# SignalGenerator.net
KiCad netlist of a schematic drawn in EAGLE
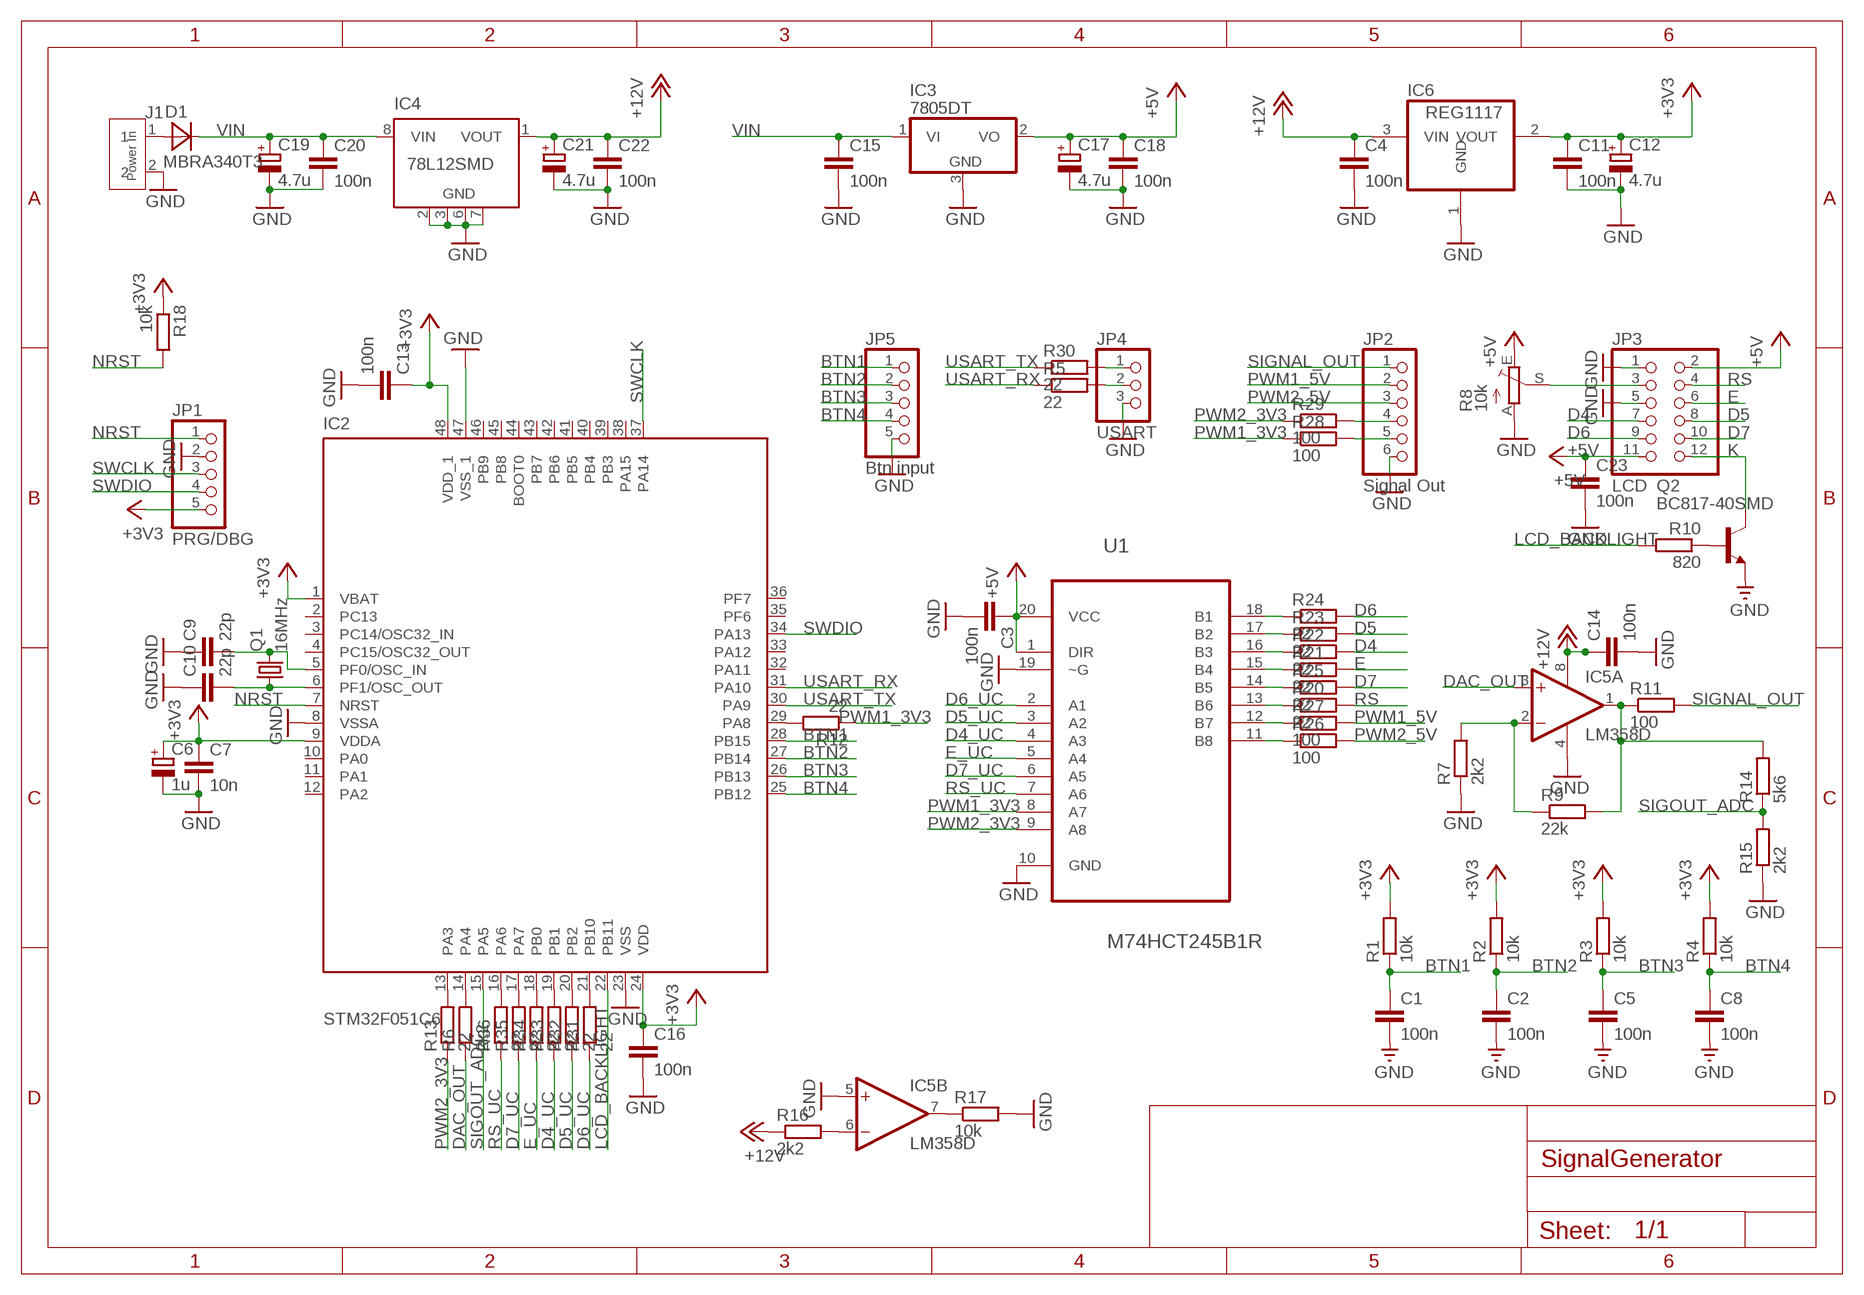
[diagram p0: schematic, sheet 1]

(export (version "E")
  (design (tool "Eeschema 10.0.6"))
  (components
    (comp (ref "C1")
      (value "100n")
      (footprint "eagle-import:C0805")
      (libsource (lib "eagle-import") (part "C-EUC0805"))
    )
    (comp (ref "C2")
      (value "100n")
      (footprint "eagle-import:C0805")
      (libsource (lib "eagle-import") (part "C-EUC0805"))
    )
    (comp (ref "C3")
      (value "100n")
      (footprint "eagle-import:C0805")
      (libsource (lib "eagle-import") (part "C-EUC0805"))
    )
    (comp (ref "C4")
      (value "100n")
      (footprint "eagle-import:C0805")
      (libsource (lib "eagle-import") (part "C-EUC0805"))
    )
    (comp (ref "C5")
      (value "100n")
      (footprint "eagle-import:C0805")
      (libsource (lib "eagle-import") (part "C-EUC0805"))
    )
    (comp (ref "C6")
      (value "1u")
      (footprint "eagle-import:A_3216-18W")
      (libsource (lib "eagle-import") (part "CPOL-EUA/3216-18W"))
    )
    (comp (ref "C7")
      (value "10n")
      (footprint "eagle-import:C0805")
      (libsource (lib "eagle-import") (part "C-EUC0805"))
    )
    (comp (ref "C8")
      (value "100n")
      (footprint "eagle-import:C0805")
      (libsource (lib "eagle-import") (part "C-EUC0805"))
    )
    (comp (ref "C9")
      (value "22p")
      (footprint "eagle-import:C0603")
      (libsource (lib "eagle-import") (part "C-EUC0603"))
    )
    (comp (ref "C10")
      (value "22p")
      (footprint "eagle-import:C0603")
      (libsource (lib "eagle-import") (part "C-EUC0603"))
    )
    (comp (ref "C11")
      (value "100n")
      (footprint "eagle-import:C0805")
      (libsource (lib "eagle-import") (part "C-EUC0805"))
    )
    (comp (ref "C12")
      (value "4.7u")
      (footprint "eagle-import:PANASONIC_A")
      (libsource (lib "eagle-import") (part "CPOL-EUA"))
    )
    (comp (ref "C13")
      (value "100n")
      (footprint "eagle-import:C0805")
      (libsource (lib "eagle-import") (part "C-EUC0805"))
    )
    (comp (ref "C14")
      (value "100n")
      (footprint "eagle-import:C0805")
      (libsource (lib "eagle-import") (part "C-EUC0805"))
    )
    (comp (ref "C15")
      (value "100n")
      (footprint "eagle-import:C0805")
      (libsource (lib "eagle-import") (part "C-EUC0805"))
    )
    (comp (ref "C16")
      (value "100n")
      (footprint "eagle-import:C0805")
      (libsource (lib "eagle-import") (part "C-EUC0805"))
    )
    (comp (ref "C17")
      (value "4.7u")
      (footprint "eagle-import:PANASONIC_B")
      (libsource (lib "eagle-import") (part "CPOL-EUB"))
    )
    (comp (ref "C18")
      (value "100n")
      (footprint "eagle-import:C0805")
      (libsource (lib "eagle-import") (part "C-EUC0805"))
    )
    (comp (ref "C19")
      (value "4.7u")
      (footprint "eagle-import:PANASONIC_B")
      (libsource (lib "eagle-import") (part "CPOL-EUB"))
    )
    (comp (ref "C20")
      (value "100n")
      (footprint "eagle-import:C0805")
      (libsource (lib "eagle-import") (part "C-EUC0805"))
    )
    (comp (ref "C21")
      (value "4.7u")
      (footprint "eagle-import:PANASONIC_A")
      (libsource (lib "eagle-import") (part "CPOL-EUA"))
    )
    (comp (ref "C22")
      (value "100n")
      (footprint "eagle-import:C0805")
      (libsource (lib "eagle-import") (part "C-EUC0805"))
    )
    (comp (ref "C23")
      (value "100n")
      (footprint "eagle-import:C0805")
      (libsource (lib "eagle-import") (part "C-EUC0805"))
    )
    (comp (ref "D1")
      (value "MBRA340T3")
      (footprint "eagle-import:SMA")
      (libsource (lib "eagle-import") (part "MBRA340T3"))
    )
    (comp (ref "IC2")
      (value "STM32F051C6")
      (footprint "eagle-import:LQFP48-7X7")
      (libsource (lib "eagle-import") (part "STM32F051C6"))
    )
    (comp (ref "IC3")
      (value "7805DT")
      (footprint "eagle-import:TO252")
      (libsource (lib "eagle-import") (part "78DT05"))
    )
    (comp (ref "IC4")
      (value "78L12SMD")
      (footprint "eagle-import:SO08")
      (libsource (lib "eagle-import") (part "78LSMD12"))
    )
    (comp (ref "IC5")
      (value "LM358D")
      (footprint "eagle-import:SO08")
      (libsource (lib "eagle-import") (part "LM358D"))
    )
    (comp (ref "IC6")
      (value "REG1117")
      (footprint "eagle-import:SOT223")
      (libsource (lib "eagle-import") (part "REG1117"))
    )
    (comp (ref "J1")
      (value "Power In")
      (footprint "eagle-import:2P-5.08")
      (libsource (lib "eagle-import") (part "SCREW-TERMINAL-2P'5.08'"))
    )
    (comp (ref "JP1")
      (value "PRG/DBG")
      (footprint "eagle-import:1X05")
      (libsource (lib "eagle-import") (part "PINHD-1X5"))
    )
    (comp (ref "JP2")
      (value "Signal Out")
      (footprint "eagle-import:1X06")
      (libsource (lib "eagle-import") (part "PINHD-1X6"))
    )
    (comp (ref "JP3")
      (value "LCD")
      (footprint "eagle-import:2X06")
      (libsource (lib "eagle-import") (part "PINHD-2X6"))
    )
    (comp (ref "JP4")
      (value "USART")
      (footprint "eagle-import:1X03")
      (libsource (lib "eagle-import") (part "PINHD-1X3"))
    )
    (comp (ref "JP5")
      (value "Btn input")
      (footprint "eagle-import:1X05")
      (libsource (lib "eagle-import") (part "PINHD-1X5"))
    )
    (comp (ref "Q1")
      (value "16MHz")
      (footprint "eagle-import:SMD_CRYSTAL")
      (libsource (lib "eagle-import") (part "SMD_CRYSTAL"))
    )
    (comp (ref "Q2")
      (value "BC817-40SMD")
      (footprint "eagle-import:SOT23-BEC")
      (libsource (lib "eagle-import") (part "BC817SMD-40"))
    )
    (comp (ref "R1")
      (value "10k")
      (footprint "eagle-import:R0603")
      (libsource (lib "eagle-import") (part "R-EU_R0603"))
    )
    (comp (ref "R2")
      (value "10k")
      (footprint "eagle-import:R0603")
      (libsource (lib "eagle-import") (part "R-EU_R0603"))
    )
    (comp (ref "R3")
      (value "10k")
      (footprint "eagle-import:R0603")
      (libsource (lib "eagle-import") (part "R-EU_R0603"))
    )
    (comp (ref "R4")
      (value "10k")
      (footprint "eagle-import:R0603")
      (libsource (lib "eagle-import") (part "R-EU_R0603"))
    )
    (comp (ref "R5")
      (value "22")
      (footprint "eagle-import:R0603")
      (libsource (lib "eagle-import") (part "R-EU_R0603"))
    )
    (comp (ref "R6")
      (value "2k2")
      (footprint "eagle-import:R0603")
      (libsource (lib "eagle-import") (part "R-EU_R0603"))
    )
    (comp (ref "R7")
      (value "2k2")
      (footprint "eagle-import:R0603")
      (libsource (lib "eagle-import") (part "R-EU_R0603"))
    )
    (comp (ref "R8")
      (value "10k")
      (footprint "eagle-import:B25P")
      (libsource (lib "eagle-import") (part "TRIM_EU-B25P"))
    )
    (comp (ref "R9")
      (value "22k")
      (footprint "eagle-import:R0603")
      (libsource (lib "eagle-import") (part "R-EU_R0603"))
    )
    (comp (ref "R10")
      (value "820")
      (footprint "eagle-import:R0603")
      (libsource (lib "eagle-import") (part "R-EU_R0603"))
    )
    (comp (ref "R11")
      (value "100")
      (footprint "eagle-import:R0603")
      (libsource (lib "eagle-import") (part "R-EU_R0603"))
    )
    (comp (ref "R12")
      (value "22")
      (footprint "eagle-import:R0603")
      (libsource (lib "eagle-import") (part "R-EU_R0603"))
    )
    (comp (ref "R13")
      (value "22")
      (footprint "eagle-import:R0603")
      (libsource (lib "eagle-import") (part "R-EU_R0603"))
    )
    (comp (ref "R14")
      (value "5k6")
      (footprint "eagle-import:R0603")
      (libsource (lib "eagle-import") (part "R-EU_R0603"))
    )
    (comp (ref "R15")
      (value "2k2")
      (footprint "eagle-import:R0603")
      (libsource (lib "eagle-import") (part "R-EU_R0603"))
    )
    (comp (ref "R16")
      (value "2k2")
      (footprint "eagle-import:R0603")
      (libsource (lib "eagle-import") (part "R-EU_R0603"))
    )
    (comp (ref "R17")
      (value "10k")
      (footprint "eagle-import:R0603")
      (libsource (lib "eagle-import") (part "R-EU_R0603"))
    )
    (comp (ref "R18")
      (value "10k")
      (footprint "eagle-import:R0603")
      (libsource (lib "eagle-import") (part "R-EU_R0603"))
    )
    (comp (ref "R20")
      (value "22")
      (footprint "eagle-import:R0603")
      (libsource (lib "eagle-import") (part "R-EU_R0603"))
    )
    (comp (ref "R21")
      (value "22")
      (footprint "eagle-import:R0603")
      (libsource (lib "eagle-import") (part "R-EU_R0603"))
    )
    (comp (ref "R22")
      (value "22")
      (footprint "eagle-import:R0603")
      (libsource (lib "eagle-import") (part "R-EU_R0603"))
    )
    (comp (ref "R23")
      (value "22")
      (footprint "eagle-import:R0603")
      (libsource (lib "eagle-import") (part "R-EU_R0603"))
    )
    (comp (ref "R24")
      (value "22")
      (footprint "eagle-import:R0603")
      (libsource (lib "eagle-import") (part "R-EU_R0603"))
    )
    (comp (ref "R25")
      (value "22")
      (footprint "eagle-import:R0603")
      (libsource (lib "eagle-import") (part "R-EU_R0603"))
    )
    (comp (ref "R26")
      (value "100")
      (footprint "eagle-import:R0603")
      (libsource (lib "eagle-import") (part "R-EU_R0603"))
    )
    (comp (ref "R27")
      (value "100")
      (footprint "eagle-import:R0603")
      (libsource (lib "eagle-import") (part "R-EU_R0603"))
    )
    (comp (ref "R28")
      (value "100")
      (footprint "eagle-import:R0603")
      (libsource (lib "eagle-import") (part "R-EU_R0603"))
    )
    (comp (ref "R29")
      (value "100")
      (footprint "eagle-import:R0603")
      (libsource (lib "eagle-import") (part "R-EU_R0603"))
    )
    (comp (ref "R30")
      (value "22")
      (footprint "eagle-import:R0603")
      (libsource (lib "eagle-import") (part "R-EU_R0603"))
    )
    (comp (ref "R31")
      (value "22")
      (footprint "eagle-import:R0603")
      (libsource (lib "eagle-import") (part "R-EU_R0603"))
    )
    (comp (ref "R32")
      (value "22")
      (footprint "eagle-import:R0603")
      (libsource (lib "eagle-import") (part "R-EU_R0603"))
    )
    (comp (ref "R33")
      (value "22")
      (footprint "eagle-import:R0603")
      (libsource (lib "eagle-import") (part "R-EU_R0603"))
    )
    (comp (ref "R34")
      (value "22")
      (footprint "eagle-import:R0603")
      (libsource (lib "eagle-import") (part "R-EU_R0603"))
    )
    (comp (ref "R35")
      (value "22")
      (footprint "eagle-import:R0603")
      (libsource (lib "eagle-import") (part "R-EU_R0603"))
    )
    (comp (ref "R36")
      (value "22")
      (footprint "eagle-import:R0603")
      (libsource (lib "eagle-import") (part "R-EU_R0603"))
    )
    (comp (ref "U1")
      (value "M74HCT245B1R")
      (footprint "eagle-import:DIP254P762X393-20")
      (libsource (lib "eagle-import") (part "M74HCT245B1R"))
    )
  )
  (nets
    (net (code "1") (name "+3V3") (class "Default")
      (node (ref "C11") (pin "1") (pinfunction "1_1") (pintype "passive"))
      (node (ref "C12") (pin "+") (pinfunction "+_+") (pintype "passive"))
      (node (ref "C13") (pin "1") (pinfunction "1_1") (pintype "passive"))
      (node (ref "C16") (pin "1") (pinfunction "1_1") (pintype "passive"))
      (node (ref "C6") (pin "+") (pinfunction "+_+") (pintype "passive"))
      (node (ref "C7") (pin "1") (pinfunction "1_1") (pintype "passive"))
      (node (ref "IC2") (pin "1") (pinfunction "VBAT_1") (pintype "power_in"))
      (node (ref "IC2") (pin "24") (pinfunction "VDD_24") (pintype "power_in"))
      (node (ref "IC2") (pin "48") (pinfunction "VDD_1_48") (pintype "power_in"))
      (node (ref "IC2") (pin "9") (pinfunction "VDDA_9") (pintype "power_in"))
      (node (ref "IC6") (pin "2") (pinfunction "VOUT_2") (pintype "output"))
      (node (ref "JP1") (pin "5") (pinfunction "5_5") (pintype "passive"))
      (node (ref "R1") (pin "2") (pinfunction "2_2") (pintype "passive"))
      (node (ref "R18") (pin "1") (pinfunction "1_1") (pintype "passive"))
      (node (ref "R2") (pin "2") (pinfunction "2_2") (pintype "passive"))
      (node (ref "R3") (pin "2") (pinfunction "2_2") (pintype "passive"))
      (node (ref "R4") (pin "2") (pinfunction "2_2") (pintype "passive"))
    )
    (net (code "2") (name "+5V") (class "Default")
      (node (ref "C17") (pin "+") (pinfunction "+_+") (pintype "passive"))
      (node (ref "C18") (pin "1") (pinfunction "1_1") (pintype "passive"))
      (node (ref "C23") (pin "1") (pinfunction "1_1") (pintype "passive"))
      (node (ref "C3") (pin "1") (pinfunction "1_1") (pintype "passive"))
      (node (ref "IC3") (pin "2") (pinfunction "VO_2") (pintype "passive"))
      (node (ref "JP3") (pin "11") (pinfunction "11_11") (pintype "passive"))
      (node (ref "JP3") (pin "2") (pinfunction "2_2") (pintype "passive"))
      (node (ref "R8") (pin "E") (pinfunction "E_E") (pintype "passive"))
      (node (ref "U1") (pin "1") (pinfunction "DIR_1") (pintype "input"))
      (node (ref "U1") (pin "20") (pinfunction "VCC_20") (pintype "power_in"))
    )
    (net (code "3") (name "+12V") (class "Default")
      (node (ref "C14") (pin "1") (pinfunction "1_1") (pintype "passive"))
      (node (ref "C21") (pin "+") (pinfunction "+_+") (pintype "passive"))
      (node (ref "C22") (pin "1") (pinfunction "1_1") (pintype "passive"))
      (node (ref "C4") (pin "1") (pinfunction "1_1") (pintype "passive"))
      (node (ref "IC4") (pin "1") (pinfunction "VOUT_1") (pintype "output"))
      (node (ref "IC5") (pin "8") (pinfunction "V+_8") (pintype "power_in"))
      (node (ref "IC6") (pin "3") (pinfunction "VIN_3") (pintype "input"))
      (node (ref "R16") (pin "1") (pinfunction "1_1") (pintype "passive"))
    )
    (net (code "4") (name "/BTN1") (class "Default")
      (node (ref "C1") (pin "1") (pinfunction "1_1") (pintype "passive"))
      (node (ref "IC2") (pin "28") (pinfunction "PB15_28") (pintype "bidirectional"))
      (node (ref "JP5") (pin "1") (pinfunction "1_1") (pintype "passive"))
      (node (ref "R1") (pin "1") (pinfunction "1_1") (pintype "passive"))
    )
    (net (code "5") (name "/BTN2") (class "Default")
      (node (ref "C2") (pin "1") (pinfunction "1_1") (pintype "passive"))
      (node (ref "IC2") (pin "27") (pinfunction "PB14_27") (pintype "bidirectional"))
      (node (ref "JP5") (pin "2") (pinfunction "2_2") (pintype "passive"))
      (node (ref "R2") (pin "1") (pinfunction "1_1") (pintype "passive"))
    )
    (net (code "6") (name "/BTN3") (class "Default")
      (node (ref "C5") (pin "1") (pinfunction "1_1") (pintype "passive"))
      (node (ref "IC2") (pin "26") (pinfunction "PB13_26") (pintype "bidirectional"))
      (node (ref "JP5") (pin "3") (pinfunction "3_3") (pintype "passive"))
      (node (ref "R3") (pin "1") (pinfunction "1_1") (pintype "passive"))
    )
    (net (code "7") (name "/BTN4") (class "Default")
      (node (ref "C8") (pin "1") (pinfunction "1_1") (pintype "passive"))
      (node (ref "IC2") (pin "25") (pinfunction "PB12_25") (pintype "bidirectional"))
      (node (ref "JP5") (pin "4") (pinfunction "4_4") (pintype "passive"))
      (node (ref "R4") (pin "1") (pinfunction "1_1") (pintype "passive"))
    )
    (net (code "8") (name "/D4") (class "Default")
      (node (ref "JP3") (pin "7") (pinfunction "7_7") (pintype "passive"))
      (node (ref "R22") (pin "2") (pinfunction "2_2") (pintype "passive"))
    )
    (net (code "9") (name "/D4_UC") (class "Default")
      (node (ref "R33") (pin "1") (pinfunction "1_1") (pintype "passive"))
      (node (ref "U1") (pin "4") (pinfunction "A3_4") (pintype "bidirectional"))
    )
    (net (code "10") (name "/D5") (class "Default")
      (node (ref "JP3") (pin "8") (pinfunction "8_8") (pintype "passive"))
      (node (ref "R23") (pin "2") (pinfunction "2_2") (pintype "passive"))
    )
    (net (code "11") (name "/D5_UC") (class "Default")
      (node (ref "R32") (pin "1") (pinfunction "1_1") (pintype "passive"))
      (node (ref "U1") (pin "3") (pinfunction "A2_3") (pintype "bidirectional"))
    )
    (net (code "12") (name "/D6") (class "Default")
      (node (ref "JP3") (pin "9") (pinfunction "9_9") (pintype "passive"))
      (node (ref "R24") (pin "2") (pinfunction "2_2") (pintype "passive"))
    )
    (net (code "13") (name "/D6_UC") (class "Default")
      (node (ref "R31") (pin "1") (pinfunction "1_1") (pintype "passive"))
      (node (ref "U1") (pin "2") (pinfunction "A1_2") (pintype "bidirectional"))
    )
    (net (code "14") (name "/D7") (class "Default")
      (node (ref "JP3") (pin "10") (pinfunction "10_10") (pintype "passive"))
      (node (ref "R25") (pin "2") (pinfunction "2_2") (pintype "passive"))
    )
    (net (code "15") (name "/D7_UC") (class "Default")
      (node (ref "R35") (pin "1") (pinfunction "1_1") (pintype "passive"))
      (node (ref "U1") (pin "6") (pinfunction "A5_6") (pintype "bidirectional"))
    )
    (net (code "16") (name "/DAC_OUT") (class "Default")
      (node (ref "IC5") (pin "3") (pinfunction "+IN_3") (pintype "input"))
      (node (ref "R6") (pin "1") (pinfunction "1_1") (pintype "passive"))
    )
    (net (code "17") (name "/E") (class "Default")
      (node (ref "JP3") (pin "6") (pinfunction "6_6") (pintype "passive"))
      (node (ref "R21") (pin "2") (pinfunction "2_2") (pintype "passive"))
    )
    (net (code "18") (name "/E_UC") (class "Default")
      (node (ref "R34") (pin "1") (pinfunction "1_1") (pintype "passive"))
      (node (ref "U1") (pin "5") (pinfunction "A4_5") (pintype "bidirectional"))
    )
    (net (code "19") (name "/K") (class "Default")
      (node (ref "JP3") (pin "12") (pinfunction "12_12") (pintype "passive"))
      (node (ref "Q2") (pin "C") (pinfunction "C_C") (pintype "passive"))
    )
    (net (code "20") (name "/LCD_BACKLIGHT") (class "Default")
      (node (ref "IC2") (pin "22") (pinfunction "PB11_22") (pintype "bidirectional"))
      (node (ref "R10") (pin "2") (pinfunction "2_2") (pintype "passive"))
    )
    (net (code "21") (name "/NRST") (class "Default")
      (node (ref "IC2") (pin "7") (pinfunction "NRST_7") (pintype "bidirectional"))
      (node (ref "JP1") (pin "1") (pinfunction "1_1") (pintype "passive"))
      (node (ref "R18") (pin "2") (pinfunction "2_2") (pintype "passive"))
    )
    (net (code "22") (name "/PWM1_3V3") (class "Default")
      (node (ref "R12") (pin "1") (pinfunction "1_1") (pintype "passive"))
      (node (ref "R28") (pin "1") (pinfunction "1_1") (pintype "passive"))
      (node (ref "U1") (pin "8") (pinfunction "A7_8") (pintype "bidirectional"))
    )
    (net (code "23") (name "/PWM1_5V") (class "Default")
      (node (ref "JP2") (pin "2") (pinfunction "2_2") (pintype "passive"))
      (node (ref "R27") (pin "2") (pinfunction "2_2") (pintype "passive"))
    )
    (net (code "24") (name "/PWM2_3V3") (class "Default")
      (node (ref "R13") (pin "1") (pinfunction "1_1") (pintype "passive"))
      (node (ref "R29") (pin "1") (pinfunction "1_1") (pintype "passive"))
      (node (ref "U1") (pin "9") (pinfunction "A8_9") (pintype "bidirectional"))
    )
    (net (code "25") (name "/PWM2_5V") (class "Default")
      (node (ref "JP2") (pin "3") (pinfunction "3_3") (pintype "passive"))
      (node (ref "R26") (pin "2") (pinfunction "2_2") (pintype "passive"))
    )
    (net (code "26") (name "/RS") (class "Default")
      (node (ref "JP3") (pin "4") (pinfunction "4_4") (pintype "passive"))
      (node (ref "R20") (pin "2") (pinfunction "2_2") (pintype "passive"))
    )
    (net (code "27") (name "/RS_UC") (class "Default")
      (node (ref "R36") (pin "1") (pinfunction "1_1") (pintype "passive"))
      (node (ref "U1") (pin "7") (pinfunction "A6_7") (pintype "bidirectional"))
    )
    (net (code "28") (name "/SIGNAL_OUT") (class "Default")
      (node (ref "JP2") (pin "1") (pinfunction "1_1") (pintype "passive"))
      (node (ref "R11") (pin "2") (pinfunction "2_2") (pintype "passive"))
    )
    (net (code "29") (name "/SIGOUT_ADC") (class "Default")
      (node (ref "IC2") (pin "15") (pinfunction "PA5_15") (pintype "bidirectional"))
      (node (ref "R14") (pin "1") (pinfunction "1_1") (pintype "passive"))
      (node (ref "R15") (pin "2") (pinfunction "2_2") (pintype "passive"))
    )
    (net (code "30") (name "/SWCLK") (class "Default")
      (node (ref "IC2") (pin "37") (pinfunction "PA14_37") (pintype "bidirectional"))
      (node (ref "JP1") (pin "3") (pinfunction "3_3") (pintype "passive"))
    )
    (net (code "31") (name "/SWDIO") (class "Default")
      (node (ref "IC2") (pin "34") (pinfunction "PA13_34") (pintype "bidirectional"))
      (node (ref "JP1") (pin "4") (pinfunction "4_4") (pintype "passive"))
    )
    (net (code "32") (name "/USART_RX") (class "Default")
      (node (ref "IC2") (pin "31") (pinfunction "PA10_31") (pintype "bidirectional"))
      (node (ref "R5") (pin "1") (pinfunction "1_1") (pintype "passive"))
    )
    (net (code "33") (name "/USART_TX") (class "Default")
      (node (ref "IC2") (pin "30") (pinfunction "PA9_30") (pintype "bidirectional"))
      (node (ref "R30") (pin "1") (pinfunction "1_1") (pintype "passive"))
    )
    (net (code "34") (name "/VIN") (class "Default")
      (node (ref "C15") (pin "1") (pinfunction "1_1") (pintype "passive"))
      (node (ref "C19") (pin "+") (pinfunction "+_+") (pintype "passive"))
      (node (ref "C20") (pin "1") (pinfunction "1_1") (pintype "passive"))
      (node (ref "D1") (pin "C") (pinfunction "C_C") (pintype "passive"))
      (node (ref "IC3") (pin "1") (pinfunction "VI_1") (pintype "input"))
      (node (ref "IC4") (pin "8") (pinfunction "VIN_8") (pintype "passive"))
    )
    (net (code "35") (name "GND") (class "Default")
      (node (ref "C1") (pin "2") (pinfunction "2_2") (pintype "passive"))
      (node (ref "C10") (pin "1") (pinfunction "1_1") (pintype "passive"))
      (node (ref "C11") (pin "2") (pinfunction "2_2") (pintype "passive"))
      (node (ref "C12") (pin "-") (pinfunction "-_-") (pintype "passive"))
      (node (ref "C13") (pin "2") (pinfunction "2_2") (pintype "passive"))
      (node (ref "C14") (pin "2") (pinfunction "2_2") (pintype "passive"))
      (node (ref "C15") (pin "2") (pinfunction "2_2") (pintype "passive"))
      (node (ref "C16") (pin "2") (pinfunction "2_2") (pintype "passive"))
      (node (ref "C17") (pin "-") (pinfunction "-_-") (pintype "passive"))
      (node (ref "C18") (pin "2") (pinfunction "2_2") (pintype "passive"))
      (node (ref "C19") (pin "-") (pinfunction "-_-") (pintype "passive"))
      (node (ref "C2") (pin "2") (pinfunction "2_2") (pintype "passive"))
      (node (ref "C20") (pin "2") (pinfunction "2_2") (pintype "passive"))
      (node (ref "C21") (pin "-") (pinfunction "-_-") (pintype "passive"))
      (node (ref "C22") (pin "2") (pinfunction "2_2") (pintype "passive"))
      (node (ref "C23") (pin "2") (pinfunction "2_2") (pintype "passive"))
      (node (ref "C3") (pin "2") (pinfunction "2_2") (pintype "passive"))
      (node (ref "C4") (pin "2") (pinfunction "2_2") (pintype "passive"))
      (node (ref "C5") (pin "2") (pinfunction "2_2") (pintype "passive"))
      (node (ref "C6") (pin "-") (pinfunction "-_-") (pintype "passive"))
      (node (ref "C7") (pin "2") (pinfunction "2_2") (pintype "passive"))
      (node (ref "C8") (pin "2") (pinfunction "2_2") (pintype "passive"))
      (node (ref "C9") (pin "1") (pinfunction "1_1") (pintype "passive"))
      (node (ref "IC2") (pin "23") (pinfunction "VSS_23") (pintype "power_in"))
      (node (ref "IC2") (pin "47") (pinfunction "VSS_1_47") (pintype "power_in"))
      (node (ref "IC2") (pin "8") (pinfunction "VSSA_8") (pintype "power_in"))
      (node (ref "IC3") (pin "3") (pinfunction "GND_3") (pintype "passive"))
      (node (ref "IC4") (pin "2") (pinfunction "GND_2") (pintype "power_in"))
      (node (ref "IC4") (pin "3") (pinfunction "GND_3") (pintype "power_in"))
      (node (ref "IC4") (pin "6") (pinfunction "GND_6") (pintype "power_in"))
      (node (ref "IC4") (pin "7") (pinfunction "GND_7") (pintype "power_in"))
      (node (ref "IC5") (pin "4") (pinfunction "V-_4") (pintype "power_in"))
      (node (ref "IC5") (pin "5") (pinfunction "+IN_5") (pintype "input"))
      (node (ref "IC6") (pin "1") (pinfunction "GND_1") (pintype "power_in"))
      (node (ref "J1") (pin "2") (pinfunction "2_2") (pintype "bidirectional"))
      (node (ref "JP1") (pin "2") (pinfunction "2_2") (pintype "passive"))
      (node (ref "JP2") (pin "6") (pinfunction "6_6") (pintype "passive"))
      (node (ref "JP3") (pin "1") (pinfunction "1_1") (pintype "passive"))
      (node (ref "JP3") (pin "5") (pinfunction "5_5") (pintype "passive"))
      (node (ref "JP4") (pin "3") (pinfunction "3_3") (pintype "passive"))
      (node (ref "JP5") (pin "5") (pinfunction "5_5") (pintype "passive"))
      (node (ref "Q2") (pin "E") (pinfunction "E_E") (pintype "passive"))
      (node (ref "R15") (pin "1") (pinfunction "1_1") (pintype "passive"))
      (node (ref "R17") (pin "2") (pinfunction "2_2") (pintype "passive"))
      (node (ref "R7") (pin "1") (pinfunction "1_1") (pintype "passive"))
      (node (ref "R8") (pin "A") (pinfunction "A_A") (pintype "passive"))
      (node (ref "U1") (pin "10") (pinfunction "GND_10") (pintype "passive"))
      (node (ref "U1") (pin "19") (pinfunction "~{G}_19") (pintype "input"))
    )
    (net (code "36") (name "Net-(D1-PadA)") (class "Default")
      (node (ref "D1") (pin "A") (pinfunction "A_A") (pintype "passive"))
      (node (ref "J1") (pin "1") (pinfunction "1_1") (pintype "bidirectional"))
    )
    (net (code "37") (name "Net-(IC2-PA3)") (class "Default")
      (node (ref "IC2") (pin "13") (pinfunction "PA3_13") (pintype "bidirectional"))
      (node (ref "R13") (pin "2") (pinfunction "2_2") (pintype "passive"))
    )
    (net (code "38") (name "Net-(IC2-PA4)") (class "Default")
      (node (ref "IC2") (pin "14") (pinfunction "PA4_14") (pintype "bidirectional"))
      (node (ref "R6") (pin "2") (pinfunction "2_2") (pintype "passive"))
    )
    (net (code "39") (name "Net-(IC2-PA6)") (class "Default")
      (node (ref "IC2") (pin "16") (pinfunction "PA6_16") (pintype "bidirectional"))
      (node (ref "R36") (pin "2") (pinfunction "2_2") (pintype "passive"))
    )
    (net (code "40") (name "Net-(IC2-PA7)") (class "Default")
      (node (ref "IC2") (pin "17") (pinfunction "PA7_17") (pintype "bidirectional"))
      (node (ref "R35") (pin "2") (pinfunction "2_2") (pintype "passive"))
    )
    (net (code "41") (name "Net-(IC2-PA8)") (class "Default")
      (node (ref "IC2") (pin "29") (pinfunction "PA8_29") (pintype "bidirectional"))
      (node (ref "R12") (pin "2") (pinfunction "2_2") (pintype "passive"))
    )
    (net (code "42") (name "Net-(IC2-PB0)") (class "Default")
      (node (ref "IC2") (pin "18") (pinfunction "PB0_18") (pintype "bidirectional"))
      (node (ref "R34") (pin "2") (pinfunction "2_2") (pintype "passive"))
    )
    (net (code "43") (name "Net-(IC2-PB1)") (class "Default")
      (node (ref "IC2") (pin "19") (pinfunction "PB1_19") (pintype "bidirectional"))
      (node (ref "R33") (pin "2") (pinfunction "2_2") (pintype "passive"))
    )
    (net (code "44") (name "Net-(IC2-PB2)") (class "Default")
      (node (ref "IC2") (pin "20") (pinfunction "PB2_20") (pintype "bidirectional"))
      (node (ref "R32") (pin "2") (pinfunction "2_2") (pintype "passive"))
    )
    (net (code "45") (name "Net-(IC2-PB10)") (class "Default")
      (node (ref "IC2") (pin "21") (pinfunction "PB10_21") (pintype "bidirectional"))
      (node (ref "R31") (pin "2") (pinfunction "2_2") (pintype "passive"))
    )
    (net (code "46") (name "Net-(IC2-PF0{slash}OSC_IN)") (class "Default")
      (node (ref "C9") (pin "2") (pinfunction "2_2") (pintype "passive"))
      (node (ref "IC2") (pin "5") (pinfunction "PF0/OSC_IN_5") (pintype "bidirectional"))
      (node (ref "Q1") (pin "2") (pinfunction "2_2") (pintype "passive"))
    )
    (net (code "47") (name "Net-(IC2-PF1{slash}OSC_OUT)") (class "Default")
      (node (ref "C10") (pin "2") (pinfunction "2_2") (pintype "passive"))
      (node (ref "IC2") (pin "6") (pinfunction "PF1/OSC_OUT_6") (pintype "power_in"))
      (node (ref "Q1") (pin "1") (pinfunction "1_1") (pintype "passive"))
    )
    (net (code "48") (name "Net-(IC5A--IN)") (class "Default")
      (node (ref "IC5") (pin "2") (pinfunction "-IN_2") (pintype "input"))
      (node (ref "R7") (pin "2") (pinfunction "2_2") (pintype "passive"))
      (node (ref "R9") (pin "1") (pinfunction "1_1") (pintype "passive"))
    )
    (net (code "49") (name "Net-(IC5A-OUT)") (class "Default")
      (node (ref "IC5") (pin "1") (pinfunction "OUT_1") (pintype "output"))
      (node (ref "R11") (pin "1") (pinfunction "1_1") (pintype "passive"))
      (node (ref "R14") (pin "2") (pinfunction "2_2") (pintype "passive"))
      (node (ref "R9") (pin "2") (pinfunction "2_2") (pintype "passive"))
    )
    (net (code "50") (name "Net-(IC5B--IN)") (class "Default")
      (node (ref "IC5") (pin "6") (pinfunction "-IN_6") (pintype "input"))
      (node (ref "R16") (pin "2") (pinfunction "2_2") (pintype "passive"))
    )
    (net (code "51") (name "Net-(IC5B-OUT)") (class "Default")
      (node (ref "IC5") (pin "7") (pinfunction "OUT_7") (pintype "output"))
      (node (ref "R17") (pin "1") (pinfunction "1_1") (pintype "passive"))
    )
    (net (code "52") (name "Net-(JP2-Pad4)") (class "Default")
      (node (ref "JP2") (pin "4") (pinfunction "4_4") (pintype "passive"))
      (node (ref "R29") (pin "2") (pinfunction "2_2") (pintype "passive"))
    )
    (net (code "53") (name "Net-(JP2-Pad5)") (class "Default")
      (node (ref "JP2") (pin "5") (pinfunction "5_5") (pintype "passive"))
      (node (ref "R28") (pin "2") (pinfunction "2_2") (pintype "passive"))
    )
    (net (code "54") (name "Net-(JP3-Pad3)") (class "Default")
      (node (ref "JP3") (pin "3") (pinfunction "3_3") (pintype "passive"))
      (node (ref "R8") (pin "S") (pinfunction "S_S") (pintype "passive"))
    )
    (net (code "55") (name "Net-(JP4-Pad1)") (class "Default")
      (node (ref "JP4") (pin "1") (pinfunction "1_1") (pintype "passive"))
      (node (ref "R30") (pin "2") (pinfunction "2_2") (pintype "passive"))
    )
    (net (code "56") (name "Net-(JP4-Pad2)") (class "Default")
      (node (ref "JP4") (pin "2") (pinfunction "2_2") (pintype "passive"))
      (node (ref "R5") (pin "2") (pinfunction "2_2") (pintype "passive"))
    )
    (net (code "57") (name "Net-(Q2-PadB)") (class "Default")
      (node (ref "Q2") (pin "B") (pinfunction "B_B") (pintype "passive"))
      (node (ref "R10") (pin "1") (pinfunction "1_1") (pintype "passive"))
    )
    (net (code "58") (name "Net-(U1-B1)") (class "Default")
      (node (ref "R24") (pin "1") (pinfunction "1_1") (pintype "passive"))
      (node (ref "U1") (pin "18") (pinfunction "B1_18") (pintype "bidirectional"))
    )
    (net (code "59") (name "Net-(U1-B2)") (class "Default")
      (node (ref "R23") (pin "1") (pinfunction "1_1") (pintype "passive"))
      (node (ref "U1") (pin "17") (pinfunction "B2_17") (pintype "bidirectional"))
    )
    (net (code "60") (name "Net-(U1-B3)") (class "Default")
      (node (ref "R22") (pin "1") (pinfunction "1_1") (pintype "passive"))
      (node (ref "U1") (pin "16") (pinfunction "B3_16") (pintype "bidirectional"))
    )
    (net (code "61") (name "Net-(U1-B4)") (class "Default")
      (node (ref "R21") (pin "1") (pinfunction "1_1") (pintype "passive"))
      (node (ref "U1") (pin "15") (pinfunction "B4_15") (pintype "bidirectional"))
    )
    (net (code "62") (name "Net-(U1-B5)") (class "Default")
      (node (ref "R25") (pin "1") (pinfunction "1_1") (pintype "passive"))
      (node (ref "U1") (pin "14") (pinfunction "B5_14") (pintype "bidirectional"))
    )
    (net (code "63") (name "Net-(U1-B6)") (class "Default")
      (node (ref "R20") (pin "1") (pinfunction "1_1") (pintype "passive"))
      (node (ref "U1") (pin "13") (pinfunction "B6_13") (pintype "bidirectional"))
    )
    (net (code "64") (name "Net-(U1-B7)") (class "Default")
      (node (ref "R27") (pin "1") (pinfunction "1_1") (pintype "passive"))
      (node (ref "U1") (pin "12") (pinfunction "B7_12") (pintype "bidirectional"))
    )
    (net (code "65") (name "Net-(U1-B8)") (class "Default")
      (node (ref "R26") (pin "1") (pinfunction "1_1") (pintype "passive"))
      (node (ref "U1") (pin "11") (pinfunction "B8_11") (pintype "bidirectional"))
    )
    (net (code "66") (name "unconnected-(IC2-BOOT0-Pad44)") (class "Default")
      (node (ref "IC2") (pin "44") (pinfunction "BOOT0_44") (pintype "bidirectional"))
    )
    (net (code "67") (name "unconnected-(IC2-PA0-Pad10)") (class "Default")
      (node (ref "IC2") (pin "10") (pinfunction "PA0_10") (pintype "bidirectional"))
    )
    (net (code "68") (name "unconnected-(IC2-PA1-Pad11)") (class "Default")
      (node (ref "IC2") (pin "11") (pinfunction "PA1_11") (pintype "bidirectional"))
    )
    (net (code "69") (name "unconnected-(IC2-PA2-Pad12)") (class "Default")
      (node (ref "IC2") (pin "12") (pinfunction "PA2_12") (pintype "bidirectional"))
    )
    (net (code "70") (name "unconnected-(IC2-PA11-Pad32)") (class "Default")
      (node (ref "IC2") (pin "32") (pinfunction "PA11_32") (pintype "bidirectional"))
    )
    (net (code "71") (name "unconnected-(IC2-PA12-Pad33)") (class "Default")
      (node (ref "IC2") (pin "33") (pinfunction "PA12_33") (pintype "bidirectional"))
    )
    (net (code "72") (name "unconnected-(IC2-PA15-Pad38)") (class "Default")
      (node (ref "IC2") (pin "38") (pinfunction "PA15_38") (pintype "bidirectional"))
    )
    (net (code "73") (name "unconnected-(IC2-PB3-Pad39)") (class "Default")
      (node (ref "IC2") (pin "39") (pinfunction "PB3_39") (pintype "bidirectional"))
    )
    (net (code "74") (name "unconnected-(IC2-PB4-Pad40)") (class "Default")
      (node (ref "IC2") (pin "40") (pinfunction "PB4_40") (pintype "bidirectional"))
    )
    (net (code "75") (name "unconnected-(IC2-PB5-Pad41)") (class "Default")
      (node (ref "IC2") (pin "41") (pinfunction "PB5_41") (pintype "bidirectional"))
    )
    (net (code "76") (name "unconnected-(IC2-PB6-Pad42)") (class "Default")
      (node (ref "IC2") (pin "42") (pinfunction "PB6_42") (pintype "bidirectional"))
    )
    (net (code "77") (name "unconnected-(IC2-PB7-Pad43)") (class "Default")
      (node (ref "IC2") (pin "43") (pinfunction "PB7_43") (pintype "bidirectional"))
    )
    (net (code "78") (name "unconnected-(IC2-PB8-Pad45)") (class "Default")
      (node (ref "IC2") (pin "45") (pinfunction "PB8_45") (pintype "bidirectional"))
    )
    (net (code "79") (name "unconnected-(IC2-PB9-Pad46)") (class "Default")
      (node (ref "IC2") (pin "46") (pinfunction "PB9_46") (pintype "bidirectional"))
    )
    (net (code "80") (name "unconnected-(IC2-PC13-Pad2)") (class "Default")
      (node (ref "IC2") (pin "2") (pinfunction "PC13_2") (pintype "bidirectional"))
    )
    (net (code "81") (name "unconnected-(IC2-PC14{slash}OSC32_IN-Pad3)") (class "Default")
      (node (ref "IC2") (pin "3") (pinfunction "PC14/OSC32_IN_3") (pintype "bidirectional"))
    )
    (net (code "82") (name "unconnected-(IC2-PC15{slash}OSC32_OUT-Pad4)") (class "Default")
      (node (ref "IC2") (pin "4") (pinfunction "PC15/OSC32_OUT_4") (pintype "bidirectional"))
    )
    (net (code "83") (name "unconnected-(IC2-PF6-Pad35)") (class "Default")
      (node (ref "IC2") (pin "35") (pinfunction "PF6_35") (pintype "bidirectional"))
    )
    (net (code "84") (name "unconnected-(IC2-PF7-Pad36)") (class "Default")
      (node (ref "IC2") (pin "36") (pinfunction "PF7_36") (pintype "bidirectional"))
    )
  )
)
